# turbidityLED.net
KiCad netlist of a schematic drawn in EAGLE
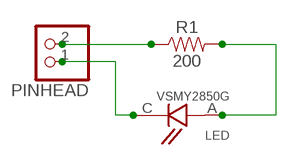
[diagram p0: schematic, sheet 1]

(export (version "E")
  (design (tool "Eeschema 10.0.6"))
  (components
    (comp (ref "LED")
      (value "VSMY2850G")
      (footprint "eagle-import:SOD4223X279N")
      (fields (field (name "MF") "Vishay Semiconductor"))
      (libsource (lib "eagle-import") (part "VSMY2850G"))
    )
    (comp (ref "PINHEAD")
      (value "PINHD-1X2")
      (footprint "eagle-import:1X02")
      (libsource (lib "eagle-import") (part "PINHD-1X2"))
    )
    (comp (ref "R1")
      (value "200")
      (footprint "eagle-import:0603")
      (libsource (lib "eagle-import") (part "200OHM-0603-1/10W-1%"))
    )
  )
  (nets
    (net (code "1") (name "Net-(LED-PadA)") (class "Default")
      (node (ref "LED") (pin "A") (pinfunction "A_A") (pintype "passive"))
      (node (ref "R1") (pin "2") (pinfunction "2_2") (pintype "passive"))
    )
    (net (code "2") (name "Net-(LED-PadC)") (class "Default")
      (node (ref "LED") (pin "C") (pinfunction "C_C") (pintype "passive"))
      (node (ref "PINHEAD") (pin "1") (pinfunction "1_1") (pintype "passive"))
    )
    (net (code "3") (name "Net-(PINHEAD-Pad2)") (class "Default")
      (node (ref "PINHEAD") (pin "2") (pinfunction "2_2") (pintype "passive"))
      (node (ref "R1") (pin "1") (pinfunction "1_1") (pintype "passive"))
    )
  )
)
